# sch.net
KiCad netlist of a schematic drawn in Altium Designer
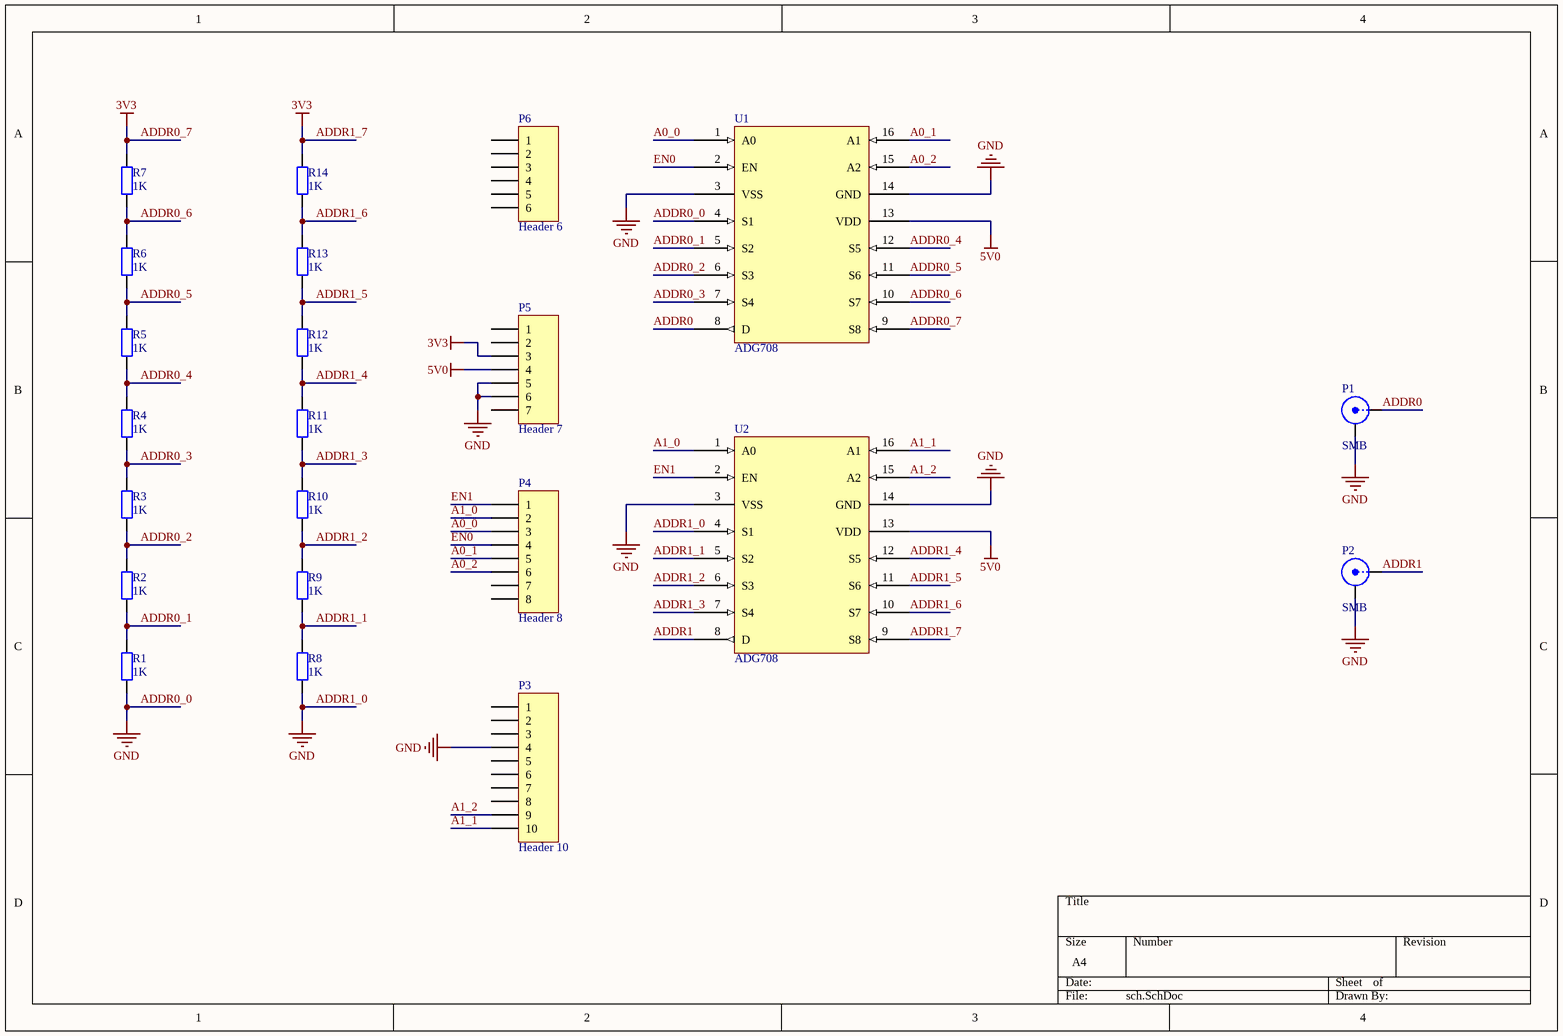
[diagram p0: sch.SchDoc]

(export (version "E")
  (design (tool "Eeschema 10.0.6"))
  (components
    (comp (ref "P1")
      (value "SMB")
      (footprint "SMB_V-RJ45")
      (description "SMB Straight Connector")
      (fields (field (name "PUBLISHER") "Altium Limited"))
      (libsource (lib "Miscellaneous Connectors") (part "SMB"))
    )
    (comp (ref "P2")
      (value "SMB")
      (footprint "SMB_V-RJ45")
      (description "SMB Straight Connector")
      (fields (field (name "PUBLISHER") "Altium Limited"))
      (libsource (lib "Miscellaneous Connectors") (part "SMB"))
    )
    (comp (ref "P3")
      (value "Header 10")
      (footprint "HDR1X10")
      (description "Header, 10-Pin")
      (fields (field (name "PUBLISHER") "Altium Limited"))
      (libsource (lib "Miscellaneous Connectors") (part "Header 10"))
    )
    (comp (ref "P4")
      (value "Header 8")
      (footprint "HDR1X8")
      (description "Header, 8-Pin")
      (fields (field (name "PUBLISHER") "Altium Limited"))
      (libsource (lib "Miscellaneous Connectors") (part "Header 8"))
    )
    (comp (ref "P5")
      (value "Header 7")
      (footprint "HDR1X7")
      (description "Header, 7-Pin")
      (fields (field (name "PUBLISHER") "Altium Limited"))
      (libsource (lib "Miscellaneous Connectors") (part "Header 7"))
    )
    (comp (ref "P6")
      (value "Header 6")
      (footprint "HDR1X6")
      (description "Header, 6-Pin")
      (fields (field (name "PUBLISHER") "Altium Limited"))
      (libsource (lib "Miscellaneous Connectors") (part "Header 6"))
    )
    (comp (ref "R1")
      (value "1K")
      (footprint "0805R")
      (description "Resistor")
      (fields (field (name "Comment") "Res2") (field (name "PUBLISHER") "Altium Limited"))
      (libsource (lib "Miscellaneous Devices") (part "Res2"))
    )
    (comp (ref "R2")
      (value "1K")
      (footprint "0805R")
      (description "Resistor")
      (fields (field (name "Comment") "Res2") (field (name "PUBLISHER") "Altium Limited"))
      (libsource (lib "Miscellaneous Devices") (part "Res2"))
    )
    (comp (ref "R3")
      (value "1K")
      (footprint "0805R")
      (description "Resistor")
      (fields (field (name "Comment") "Res2") (field (name "PUBLISHER") "Altium Limited"))
      (libsource (lib "Miscellaneous Devices") (part "Res2"))
    )
    (comp (ref "R4")
      (value "1K")
      (footprint "0805R")
      (description "Resistor")
      (fields (field (name "Comment") "Res2") (field (name "PUBLISHER") "Altium Limited"))
      (libsource (lib "Miscellaneous Devices") (part "Res2"))
    )
    (comp (ref "R5")
      (value "1K")
      (footprint "0805R")
      (description "Resistor")
      (fields (field (name "Comment") "Res2") (field (name "PUBLISHER") "Altium Limited"))
      (libsource (lib "Miscellaneous Devices") (part "Res2"))
    )
    (comp (ref "R6")
      (value "1K")
      (footprint "0805R")
      (description "Resistor")
      (fields (field (name "Comment") "Res2") (field (name "PUBLISHER") "Altium Limited"))
      (libsource (lib "Miscellaneous Devices") (part "Res2"))
    )
    (comp (ref "R7")
      (value "1K")
      (footprint "0805:0805R")
      (description "Resistor")
      (fields (field (name "Comment") "Res2") (field (name "PUBLISHER") "Altium Limited"))
      (libsource (lib "Miscellaneous Devices") (part "Res2"))
    )
    (comp (ref "R8")
      (value "1K")
      (footprint "0805R")
      (description "Resistor")
      (fields (field (name "Comment") "Res2") (field (name "PUBLISHER") "Altium Limited"))
      (libsource (lib "Miscellaneous Devices") (part "Res2"))
    )
    (comp (ref "R9")
      (value "1K")
      (footprint "0805:0805R")
      (description "Resistor")
      (fields (field (name "Comment") "Res2") (field (name "PUBLISHER") "Altium Limited"))
      (libsource (lib "Miscellaneous Devices") (part "Res2"))
    )
    (comp (ref "R10")
      (value "1K")
      (footprint "0805R")
      (description "Resistor")
      (fields (field (name "Comment") "Res2") (field (name "PUBLISHER") "Altium Limited"))
      (libsource (lib "Miscellaneous Devices") (part "Res2"))
    )
    (comp (ref "R11")
      (value "1K")
      (footprint "0805R")
      (description "Resistor")
      (fields (field (name "Comment") "Res2") (field (name "PUBLISHER") "Altium Limited"))
      (libsource (lib "Miscellaneous Devices") (part "Res2"))
    )
    (comp (ref "R12")
      (value "1K")
      (footprint "0805R")
      (description "Resistor")
      (fields (field (name "Comment") "Res2") (field (name "PUBLISHER") "Altium Limited"))
      (libsource (lib "Miscellaneous Devices") (part "Res2"))
    )
    (comp (ref "R13")
      (value "1K")
      (footprint "0805:0805R")
      (description "Resistor")
      (fields (field (name "Comment") "Res2") (field (name "PUBLISHER") "Altium Limited"))
      (libsource (lib "Miscellaneous Devices") (part "Res2"))
    )
    (comp (ref "R14")
      (value "1K")
      (footprint "0805:0805R")
      (description "Resistor")
      (fields (field (name "Comment") "Res2") (field (name "PUBLISHER") "Altium Limited"))
      (libsource (lib "Miscellaneous Devices") (part "Res2"))
    )
    (comp (ref "U1") (value "ADG708") (footprint "TSSOP16") (libsource (lib "schLib") (part "ADG708")))
    (comp (ref "U2") (value "ADG708") (footprint "TSSOP16") (libsource (lib "schLib") (part "ADG708")))
  )
  (nets
    (net (code "1") (name "/A0_0") (class "Default")
      (node (ref "P4") (pin "3") (pinfunction "3_3") (pintype "passive"))
      (node (ref "U1") (pin "1") (pinfunction "A0_1") (pintype "input"))
    )
    (net (code "2") (name "/A0_1") (class "Default")
      (node (ref "P4") (pin "5") (pinfunction "5_5") (pintype "passive"))
      (node (ref "U1") (pin "16") (pinfunction "A1_16") (pintype "input"))
    )
    (net (code "3") (name "/A0_2") (class "Default")
      (node (ref "P4") (pin "6") (pinfunction "6_6") (pintype "passive"))
      (node (ref "U1") (pin "15") (pinfunction "A2_15") (pintype "input"))
    )
    (net (code "4") (name "/A1_0") (class "Default")
      (node (ref "P4") (pin "2") (pinfunction "2_2") (pintype "passive"))
      (node (ref "U2") (pin "1") (pinfunction "A0_1") (pintype "input"))
    )
    (net (code "5") (name "/A1_1") (class "Default")
      (node (ref "P3") (pin "10") (pinfunction "10_10") (pintype "passive"))
      (node (ref "U2") (pin "16") (pinfunction "A1_16") (pintype "input"))
    )
    (net (code "6") (name "/A1_2") (class "Default")
      (node (ref "P3") (pin "9") (pinfunction "9_9") (pintype "passive"))
      (node (ref "U2") (pin "15") (pinfunction "A2_15") (pintype "input"))
    )
    (net (code "7") (name "/ADDR0") (class "Default")
      (node (ref "P1") (pin "1") (pinfunction "X_1") (pintype "passive"))
      (node (ref "U1") (pin "8") (pinfunction "D_8") (pintype "output"))
    )
    (net (code "8") (name "/ADDR0_1") (class "Default")
      (node (ref "R1") (pin "2") (pinfunction "2_2") (pintype "passive"))
      (node (ref "R2") (pin "1") (pinfunction "1_1") (pintype "passive"))
      (node (ref "U1") (pin "5") (pinfunction "S2_5") (pintype "input"))
    )
    (net (code "9") (name "/ADDR0_2") (class "Default")
      (node (ref "R2") (pin "2") (pinfunction "2_2") (pintype "passive"))
      (node (ref "R3") (pin "1") (pinfunction "1_1") (pintype "passive"))
      (node (ref "U1") (pin "6") (pinfunction "S3_6") (pintype "input"))
    )
    (net (code "10") (name "/ADDR0_3") (class "Default")
      (node (ref "R3") (pin "2") (pinfunction "2_2") (pintype "passive"))
      (node (ref "R4") (pin "1") (pinfunction "1_1") (pintype "passive"))
      (node (ref "U1") (pin "7") (pinfunction "S4_7") (pintype "input"))
    )
    (net (code "11") (name "/ADDR0_4") (class "Default")
      (node (ref "R4") (pin "2") (pinfunction "2_2") (pintype "passive"))
      (node (ref "R5") (pin "1") (pinfunction "1_1") (pintype "passive"))
      (node (ref "U1") (pin "12") (pinfunction "S5_12") (pintype "input"))
    )
    (net (code "12") (name "/ADDR0_5") (class "Default")
      (node (ref "R5") (pin "2") (pinfunction "2_2") (pintype "passive"))
      (node (ref "R6") (pin "1") (pinfunction "1_1") (pintype "passive"))
      (node (ref "U1") (pin "11") (pinfunction "S6_11") (pintype "input"))
    )
    (net (code "13") (name "/ADDR0_6") (class "Default")
      (node (ref "R6") (pin "2") (pinfunction "2_2") (pintype "passive"))
      (node (ref "R7") (pin "1") (pinfunction "1_1") (pintype "passive"))
      (node (ref "U1") (pin "10") (pinfunction "S7_10") (pintype "input"))
    )
    (net (code "14") (name "/ADDR1") (class "Default")
      (node (ref "P2") (pin "1") (pinfunction "X_1") (pintype "passive"))
      (node (ref "U2") (pin "8") (pinfunction "D_8") (pintype "output"))
    )
    (net (code "15") (name "/ADDR1_1") (class "Default")
      (node (ref "R8") (pin "2") (pinfunction "2_2") (pintype "passive"))
      (node (ref "R9") (pin "1") (pinfunction "1_1") (pintype "passive"))
      (node (ref "U2") (pin "5") (pinfunction "S2_5") (pintype "input"))
    )
    (net (code "16") (name "/ADDR1_2") (class "Default")
      (node (ref "R10") (pin "1") (pinfunction "1_1") (pintype "passive"))
      (node (ref "R9") (pin "2") (pinfunction "2_2") (pintype "passive"))
      (node (ref "U2") (pin "6") (pinfunction "S3_6") (pintype "input"))
    )
    (net (code "17") (name "/ADDR1_3") (class "Default")
      (node (ref "R10") (pin "2") (pinfunction "2_2") (pintype "passive"))
      (node (ref "R11") (pin "1") (pinfunction "1_1") (pintype "passive"))
      (node (ref "U2") (pin "7") (pinfunction "S4_7") (pintype "input"))
    )
    (net (code "18") (name "/ADDR1_4") (class "Default")
      (node (ref "R11") (pin "2") (pinfunction "2_2") (pintype "passive"))
      (node (ref "R12") (pin "1") (pinfunction "1_1") (pintype "passive"))
      (node (ref "U2") (pin "12") (pinfunction "S5_12") (pintype "input"))
    )
    (net (code "19") (name "/ADDR1_5") (class "Default")
      (node (ref "R12") (pin "2") (pinfunction "2_2") (pintype "passive"))
      (node (ref "R13") (pin "1") (pinfunction "1_1") (pintype "passive"))
      (node (ref "U2") (pin "11") (pinfunction "S6_11") (pintype "input"))
    )
    (net (code "20") (name "/ADDR1_6") (class "Default")
      (node (ref "R13") (pin "2") (pinfunction "2_2") (pintype "passive"))
      (node (ref "R14") (pin "1") (pinfunction "1_1") (pintype "passive"))
      (node (ref "U2") (pin "10") (pinfunction "S7_10") (pintype "input"))
    )
    (net (code "21") (name "/EN0") (class "Default")
      (node (ref "P4") (pin "4") (pinfunction "4_4") (pintype "passive"))
      (node (ref "U1") (pin "2") (pinfunction "EN_2") (pintype "input"))
    )
    (net (code "22") (name "/EN1") (class "Default")
      (node (ref "P4") (pin "1") (pinfunction "1_1") (pintype "passive"))
      (node (ref "U2") (pin "2") (pinfunction "EN_2") (pintype "input"))
    )
    (net (code "23") (name "3V3") (class "Default")
      (node (ref "P5") (pin "3") (pinfunction "3_3") (pintype "passive"))
      (node (ref "R14") (pin "2") (pinfunction "2_2") (pintype "passive"))
      (node (ref "R7") (pin "2") (pinfunction "2_2") (pintype "passive"))
      (node (ref "U1") (pin "9") (pinfunction "S8_9") (pintype "input"))
      (node (ref "U2") (pin "9") (pinfunction "S8_9") (pintype "input"))
    )
    (net (code "24") (name "5V0") (class "Default")
      (node (ref "P5") (pin "4") (pinfunction "4_4") (pintype "passive"))
      (node (ref "U1") (pin "13") (pinfunction "VDD_13") (pintype "power_in"))
      (node (ref "U2") (pin "13") (pinfunction "VDD_13") (pintype "power_in"))
    )
    (net (code "25") (name "GND") (class "Default")
      (node (ref "P1") (pin "2") (pinfunction "Y_2") (pintype "passive"))
      (node (ref "P2") (pin "2") (pinfunction "Y_2") (pintype "passive"))
      (node (ref "P3") (pin "4") (pinfunction "4_4") (pintype "passive"))
      (node (ref "P5") (pin "5") (pinfunction "5_5") (pintype "passive"))
      (node (ref "P5") (pin "6") (pinfunction "6_6") (pintype "passive"))
      (node (ref "R1") (pin "1") (pinfunction "1_1") (pintype "passive"))
      (node (ref "R8") (pin "1") (pinfunction "1_1") (pintype "passive"))
      (node (ref "U1") (pin "14") (pinfunction "GND_14") (pintype "power_in"))
      (node (ref "U1") (pin "3") (pinfunction "VSS_3") (pintype "power_in"))
      (node (ref "U1") (pin "4") (pinfunction "S1_4") (pintype "input"))
      (node (ref "U2") (pin "14") (pinfunction "GND_14") (pintype "power_in"))
      (node (ref "U2") (pin "3") (pinfunction "VSS_3") (pintype "power_in"))
      (node (ref "U2") (pin "4") (pinfunction "S1_4") (pintype "input"))
    )
    (net (code "26") (name "unconnected-(P3-Pad1)") (class "Default")
      (node (ref "P3") (pin "1") (pinfunction "1_1") (pintype "passive"))
    )
    (net (code "27") (name "unconnected-(P3-Pad2)") (class "Default")
      (node (ref "P3") (pin "2") (pinfunction "2_2") (pintype "passive"))
    )
    (net (code "28") (name "unconnected-(P3-Pad3)") (class "Default")
      (node (ref "P3") (pin "3") (pinfunction "3_3") (pintype "passive"))
    )
    (net (code "29") (name "unconnected-(P3-Pad5)") (class "Default")
      (node (ref "P3") (pin "5") (pinfunction "5_5") (pintype "passive"))
    )
    (net (code "30") (name "unconnected-(P3-Pad6)") (class "Default")
      (node (ref "P3") (pin "6") (pinfunction "6_6") (pintype "passive"))
    )
    (net (code "31") (name "unconnected-(P3-Pad7)") (class "Default")
      (node (ref "P3") (pin "7") (pinfunction "7_7") (pintype "passive"))
    )
    (net (code "32") (name "unconnected-(P3-Pad8)") (class "Default")
      (node (ref "P3") (pin "8") (pinfunction "8_8") (pintype "passive"))
    )
    (net (code "33") (name "unconnected-(P4-Pad7)") (class "Default")
      (node (ref "P4") (pin "7") (pinfunction "7_7") (pintype "passive"))
    )
    (net (code "34") (name "unconnected-(P4-Pad8)") (class "Default")
      (node (ref "P4") (pin "8") (pinfunction "8_8") (pintype "passive"))
    )
    (net (code "35") (name "unconnected-(P5-Pad1)") (class "Default")
      (node (ref "P5") (pin "1") (pinfunction "1_1") (pintype "passive"))
    )
    (net (code "36") (name "unconnected-(P5-Pad2)") (class "Default")
      (node (ref "P5") (pin "2") (pinfunction "2_2") (pintype "passive"))
    )
    (net (code "37") (name "unconnected-(P5-Pad7)") (class "Default")
      (node (ref "P5") (pin "7") (pinfunction "7_7") (pintype "passive"))
    )
    (net (code "38") (name "unconnected-(P6-Pad1)") (class "Default")
      (node (ref "P6") (pin "1") (pinfunction "1_1") (pintype "passive"))
    )
    (net (code "39") (name "unconnected-(P6-Pad2)") (class "Default")
      (node (ref "P6") (pin "2") (pinfunction "2_2") (pintype "passive"))
    )
    (net (code "40") (name "unconnected-(P6-Pad3)") (class "Default")
      (node (ref "P6") (pin "3") (pinfunction "3_3") (pintype "passive"))
    )
    (net (code "41") (name "unconnected-(P6-Pad4)") (class "Default")
      (node (ref "P6") (pin "4") (pinfunction "4_4") (pintype "passive"))
    )
    (net (code "42") (name "unconnected-(P6-Pad5)") (class "Default")
      (node (ref "P6") (pin "5") (pinfunction "5_5") (pintype "passive"))
    )
    (net (code "43") (name "unconnected-(P6-Pad6)") (class "Default")
      (node (ref "P6") (pin "6") (pinfunction "6_6") (pintype "passive"))
    )
  )
)
